# OpenServoCAN_Power_Board_V_1_0_1.net
KiCad netlist of a schematic drawn in EAGLE
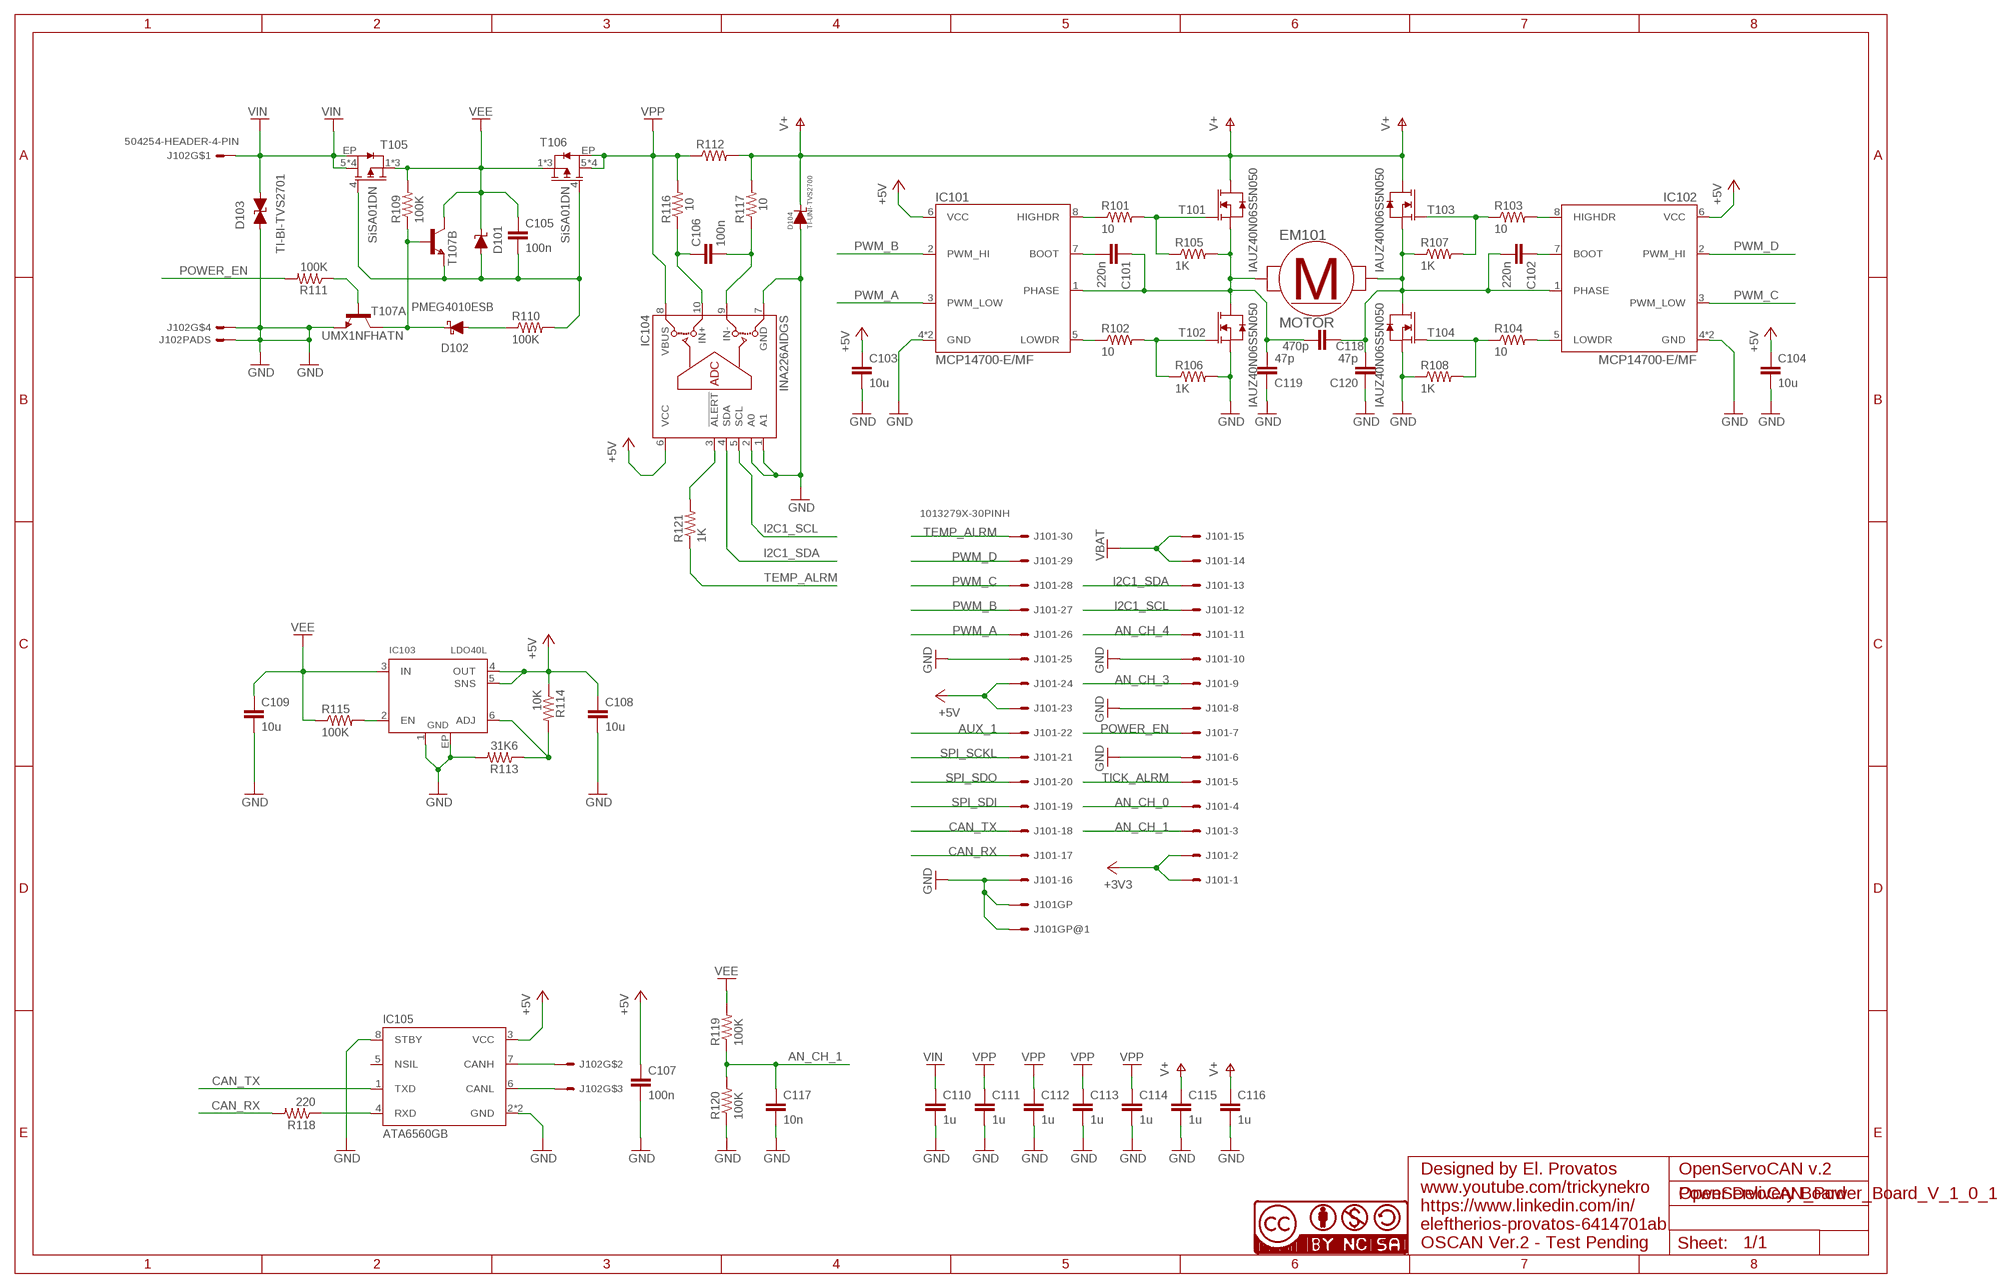
[diagram p0: schematic, sheet 1]

(export (version "E")
  (design (tool "Eeschema 10.0.6"))
  (components
    (comp (ref "C101")
      (value "220n")
      (footprint "eagle-import:0603_C")
      (libsource (lib "eagle-import") (part "C-EUC0603"))
    )
    (comp (ref "C102")
      (value "220n")
      (footprint "eagle-import:0603_C")
      (libsource (lib "eagle-import") (part "C-EUC0603"))
    )
    (comp (ref "C103")
      (value "10u")
      (footprint "eagle-import:0402_C")
      (libsource (lib "eagle-import") (part "C-EUC0402"))
    )
    (comp (ref "C104")
      (value "10u")
      (footprint "eagle-import:0402_C")
      (libsource (lib "eagle-import") (part "C-EUC0402"))
    )
    (comp (ref "C105")
      (value "100n")
      (footprint "eagle-import:0402_C")
      (libsource (lib "eagle-import") (part "C-EUC0402"))
    )
    (comp (ref "C106")
      (value "100n")
      (footprint "eagle-import:0402_C")
      (libsource (lib "eagle-import") (part "C-EUC0402"))
    )
    (comp (ref "C107")
      (value "100n")
      (footprint "eagle-import:0402_C")
      (libsource (lib "eagle-import") (part "C-EUC0402"))
    )
    (comp (ref "C108")
      (value "10u")
      (footprint "eagle-import:0402_C")
      (libsource (lib "eagle-import") (part "C-EUC0402"))
    )
    (comp (ref "C109")
      (value "10u")
      (footprint "eagle-import:0402_C")
      (libsource (lib "eagle-import") (part "C-EUC0402"))
    )
    (comp (ref "C110")
      (value "1u")
      (footprint "eagle-import:0603_C")
      (libsource (lib "eagle-import") (part "C-EUC0603"))
    )
    (comp (ref "C111")
      (value "1u")
      (footprint "eagle-import:0603_C")
      (libsource (lib "eagle-import") (part "C-EUC0603"))
    )
    (comp (ref "C112")
      (value "1u")
      (footprint "eagle-import:0603_C")
      (libsource (lib "eagle-import") (part "C-EUC0603"))
    )
    (comp (ref "C113")
      (value "1u")
      (footprint "eagle-import:0603_C")
      (libsource (lib "eagle-import") (part "C-EUC0603"))
    )
    (comp (ref "C114")
      (value "1u")
      (footprint "eagle-import:0603_C")
      (libsource (lib "eagle-import") (part "C-EUC0603"))
    )
    (comp (ref "C115")
      (value "1u")
      (footprint "eagle-import:0603_C")
      (libsource (lib "eagle-import") (part "C-EUC0603"))
    )
    (comp (ref "C116")
      (value "1u")
      (footprint "eagle-import:0603_C")
      (libsource (lib "eagle-import") (part "C-EUC0603"))
    )
    (comp (ref "C117")
      (value "10n")
      (footprint "eagle-import:0402_C")
      (libsource (lib "eagle-import") (part "C-EUC0402"))
    )
    (comp (ref "C118")
      (value "470p")
      (footprint "eagle-import:1206_C")
      (libsource (lib "eagle-import") (part "C-EUC1206"))
    )
    (comp (ref "C119")
      (value "47p")
      (footprint "eagle-import:1206_C")
      (libsource (lib "eagle-import") (part "C-EUC1206"))
    )
    (comp (ref "C120")
      (value "47p")
      (footprint "eagle-import:1206_C")
      (libsource (lib "eagle-import") (part "C-EUC1206"))
    )
    (comp (ref "D101")
      (value "DDZ12CSF")
      (footprint "eagle-import:SOD-323")
      (libsource (lib "eagle-import") (part "DDZ12CSF"))
    )
    (comp (ref "D102")
      (value "PMEG4010ESB")
      (footprint "eagle-import:DSN1006-2")
      (libsource (lib "eagle-import") (part "PMEG4010ESB"))
    )
    (comp (ref "D103")
      (value "TI-BI-TVS2701")
      (footprint "eagle-import:VSON-8-DRB0008A")
      (libsource (lib "eagle-import") (part "TI-BI-TVS2701"))
    )
    (comp (ref "D104")
      (value "TI-UNI-TVS2700")
      (footprint "eagle-import:WSON-6")
      (libsource (lib "eagle-import") (part "TI-UNI-TVS2700"))
    )
    (comp (ref "EM101")
      (value "MOTOR")
      (footprint "eagle-import:RF-020TH-10210")
      (libsource (lib "eagle-import") (part "MOTOR"))
    )
    (comp (ref "IC101")
      (value "MCP14700-E/MF")
      (footprint "eagle-import:DFN_8_3X3X09_MF_MICROCHIP")
      (libsource (lib "eagle-import") (part "MCP14700-E/MF"))
    )
    (comp (ref "IC102")
      (value "MCP14700-E/MF")
      (footprint "eagle-import:DFN_8_3X3X09_MF_MICROCHIP")
      (libsource (lib "eagle-import") (part "MCP14700-E/MF"))
    )
    (comp (ref "IC103")
      (value "LDO40L")
      (footprint "eagle-import:DFN6-3X3")
      (libsource (lib "eagle-import") (part "LDO40L-ADJ"))
    )
    (comp (ref "IC104")
      (value "INA226AIDGS")
      (footprint "eagle-import:VSSOP-10")
      (libsource (lib "eagle-import") (part "INA226AIDGS"))
    )
    (comp (ref "IC105")
      (value "ATA6560GB")
      (footprint "eagle-import:VDFN-8-EP")
      (libsource (lib "eagle-import") (part "ATA6560GB"))
    )
    (comp (ref "J101")
      (value "1013279X-30PINH")
      (footprint "eagle-import:10132797-30")
      (libsource (lib "eagle-import") (part "1013279X-30PINH"))
    )
    (comp (ref "J102")
      (value "504254-HEADER-4-PIN")
      (footprint "eagle-import:504254")
      (libsource (lib "eagle-import") (part "504254-HEADER-4-PIN"))
    )
    (comp (ref "R101")
      (value "10")
      (footprint "eagle-import:0402_R")
      (libsource (lib "eagle-import") (part "R-USR0402"))
    )
    (comp (ref "R102")
      (value "10")
      (footprint "eagle-import:0402_R")
      (libsource (lib "eagle-import") (part "R-USR0402"))
    )
    (comp (ref "R103")
      (value "10")
      (footprint "eagle-import:0402_R")
      (libsource (lib "eagle-import") (part "R-USR0402"))
    )
    (comp (ref "R104")
      (value "10")
      (footprint "eagle-import:0402_R")
      (libsource (lib "eagle-import") (part "R-USR0402"))
    )
    (comp (ref "R105")
      (value "1K")
      (footprint "eagle-import:0402_R")
      (libsource (lib "eagle-import") (part "R-USR0402"))
    )
    (comp (ref "R106")
      (value "1K")
      (footprint "eagle-import:0402_R")
      (libsource (lib "eagle-import") (part "R-USR0402"))
    )
    (comp (ref "R107")
      (value "1K")
      (footprint "eagle-import:0402_R")
      (libsource (lib "eagle-import") (part "R-USR0402"))
    )
    (comp (ref "R108")
      (value "1K")
      (footprint "eagle-import:0402_R")
      (libsource (lib "eagle-import") (part "R-USR0402"))
    )
    (comp (ref "R109")
      (value "100K")
      (footprint "eagle-import:0402_R")
      (libsource (lib "eagle-import") (part "R-USR0402"))
    )
    (comp (ref "R110")
      (value "100K")
      (footprint "eagle-import:0402_R")
      (libsource (lib "eagle-import") (part "R-USR0402"))
    )
    (comp (ref "R111")
      (value "100K")
      (footprint "eagle-import:0402_R")
      (libsource (lib "eagle-import") (part "R-USR0402"))
    )
    (comp (ref "R112")
      (value "TLR2HW-R-US-SENSE")
      (footprint "eagle-import:TLR2HW")
      (libsource (lib "eagle-import") (part "TLR2HW-R-US-SENSE"))
    )
    (comp (ref "R113")
      (value "31K6")
      (footprint "eagle-import:0402_R")
      (libsource (lib "eagle-import") (part "R-USR0402"))
    )
    (comp (ref "R114")
      (value "10K")
      (footprint "eagle-import:0402_R")
      (libsource (lib "eagle-import") (part "R-USR0402"))
    )
    (comp (ref "R115")
      (value "100K")
      (footprint "eagle-import:0402_R")
      (libsource (lib "eagle-import") (part "R-USR0402"))
    )
    (comp (ref "R116")
      (value "10")
      (footprint "eagle-import:0402_R")
      (libsource (lib "eagle-import") (part "R-USR0402"))
    )
    (comp (ref "R117")
      (value "10")
      (footprint "eagle-import:0402_R")
      (libsource (lib "eagle-import") (part "R-USR0402"))
    )
    (comp (ref "R118")
      (value "220")
      (footprint "eagle-import:0402_R")
      (libsource (lib "eagle-import") (part "R-USR0402"))
    )
    (comp (ref "R119")
      (value "100K")
      (footprint "eagle-import:0402_R")
      (libsource (lib "eagle-import") (part "R-USR0402"))
    )
    (comp (ref "R120")
      (value "100K")
      (footprint "eagle-import:0402_R")
      (libsource (lib "eagle-import") (part "R-USR0402"))
    )
    (comp (ref "R121")
      (value "1K")
      (footprint "eagle-import:0402_R")
      (libsource (lib "eagle-import") (part "R-USR0402"))
    )
    (comp (ref "T101")
      (value "IAUZ40N06S5N050")
      (footprint "eagle-import:PG-TSDSON-8-33-INF")
      (libsource (lib "eagle-import") (part "IAUZ40N06S5N050"))
    )
    (comp (ref "T102")
      (value "IAUZ40N06S5N050")
      (footprint "eagle-import:PG-TSDSON-8-33-INF")
      (libsource (lib "eagle-import") (part "IAUZ40N06S5N050"))
    )
    (comp (ref "T103")
      (value "IAUZ40N06S5N050")
      (footprint "eagle-import:PG-TSDSON-8-33-INF")
      (libsource (lib "eagle-import") (part "IAUZ40N06S5N050"))
    )
    (comp (ref "T104")
      (value "IAUZ40N06S5N050")
      (footprint "eagle-import:PG-TSDSON-8-33-INF")
      (libsource (lib "eagle-import") (part "IAUZ40N06S5N050"))
    )
    (comp (ref "T105")
      (value "SiSA01DN")
      (footprint "eagle-import:POWERPAK-1212-8-SINGLE")
      (libsource (lib "eagle-import") (part "SISA01DN"))
    )
    (comp (ref "T106")
      (value "SiSA01DN")
      (footprint "eagle-import:POWERPAK-1212-8-SINGLE")
      (libsource (lib "eagle-import") (part "SISA01DN"))
    )
    (comp (ref "T107")
      (value "UMX1NFHATN")
      (footprint "eagle-import:SC-70-6")
      (libsource (lib "eagle-import") (part "UMX1NFHATN"))
    )
    (comp (ref "U$1")
      (value "CC-NC-BCNIX")
      (footprint "eagle-import:CC-NC-B_NIX")
      (libsource (lib "eagle-import") (part "CC-NC-BCNIX"))
    )
  )
  (nets
    (net (code "1") (name "+3V3") (class "Default")
      (node (ref "J101") (pin "1") (pinfunction "S_1") (pintype "passive"))
      (node (ref "J101") (pin "2") (pinfunction "S_2") (pintype "passive"))
    )
    (net (code "2") (name "+5V") (class "Default")
      (node (ref "C103") (pin "1") (pinfunction "1_1") (pintype "passive"))
      (node (ref "C104") (pin "1") (pinfunction "1_1") (pintype "passive"))
      (node (ref "C107") (pin "1") (pinfunction "1_1") (pintype "passive"))
      (node (ref "C108") (pin "1") (pinfunction "1_1") (pintype "passive"))
      (node (ref "IC101") (pin "6") (pinfunction "VCC_6") (pintype "bidirectional"))
      (node (ref "IC102") (pin "6") (pinfunction "VCC_6") (pintype "bidirectional"))
      (node (ref "IC103") (pin "4") (pinfunction "OUT_4") (pintype "bidirectional"))
      (node (ref "IC103") (pin "5") (pinfunction "SNS_5") (pintype "bidirectional"))
      (node (ref "IC104") (pin "6") (pinfunction "VCC_6") (pintype "bidirectional"))
      (node (ref "IC105") (pin "3") (pinfunction "VCC_3") (pintype "power_in"))
      (node (ref "J101") (pin "23") (pinfunction "S_23") (pintype "passive"))
      (node (ref "J101") (pin "24") (pinfunction "S_24") (pintype "passive"))
      (node (ref "R114") (pin "1") (pinfunction "1_1") (pintype "passive"))
    )
    (net (code "3") (name "/AN_CH_0") (class "Default")
      (node (ref "J101") (pin "4") (pinfunction "S_4") (pintype "passive"))
    )
    (net (code "4") (name "/AN_CH_1") (class "Default")
      (node (ref "C117") (pin "1") (pinfunction "1_1") (pintype "passive"))
      (node (ref "J101") (pin "3") (pinfunction "S_3") (pintype "passive"))
      (node (ref "R119") (pin "1") (pinfunction "1_1") (pintype "passive"))
      (node (ref "R120") (pin "2") (pinfunction "2_2") (pintype "passive"))
    )
    (net (code "5") (name "/AN_CH_3") (class "Default")
      (node (ref "J101") (pin "9") (pinfunction "S_9") (pintype "passive"))
    )
    (net (code "6") (name "/AN_CH_4") (class "Default")
      (node (ref "J101") (pin "11") (pinfunction "S_11") (pintype "passive"))
    )
    (net (code "7") (name "/AUX_1") (class "Default")
      (node (ref "J101") (pin "22") (pinfunction "S_22") (pintype "passive"))
    )
    (net (code "8") (name "/CAN_RX") (class "Default")
      (node (ref "J101") (pin "17") (pinfunction "S_17") (pintype "passive"))
      (node (ref "R118") (pin "2") (pinfunction "2_2") (pintype "passive"))
    )
    (net (code "9") (name "/CAN_TX") (class "Default")
      (node (ref "IC105") (pin "1") (pinfunction "TXD_1") (pintype "input"))
      (node (ref "J101") (pin "18") (pinfunction "S_18") (pintype "passive"))
    )
    (net (code "10") (name "/I2C1_SCL") (class "Default")
      (node (ref "IC104") (pin "5") (pinfunction "SCL_5") (pintype "bidirectional"))
      (node (ref "J101") (pin "12") (pinfunction "S_12") (pintype "passive"))
    )
    (net (code "11") (name "/I2C1_SDA") (class "Default")
      (node (ref "IC104") (pin "4") (pinfunction "SDA_4") (pintype "bidirectional"))
      (node (ref "J101") (pin "13") (pinfunction "S_13") (pintype "passive"))
    )
    (net (code "12") (name "/POWER_EN") (class "Default")
      (node (ref "J101") (pin "7") (pinfunction "S_7") (pintype "passive"))
      (node (ref "R111") (pin "2") (pinfunction "2_2") (pintype "passive"))
    )
    (net (code "13") (name "/PWM_A") (class "Default")
      (node (ref "IC101") (pin "3") (pinfunction "PWM_LOW_3") (pintype "bidirectional"))
      (node (ref "J101") (pin "26") (pinfunction "S_26") (pintype "passive"))
    )
    (net (code "14") (name "/PWM_B") (class "Default")
      (node (ref "IC101") (pin "2") (pinfunction "PWM_HI_2") (pintype "bidirectional"))
      (node (ref "J101") (pin "27") (pinfunction "S_27") (pintype "passive"))
    )
    (net (code "15") (name "/PWM_C") (class "Default")
      (node (ref "IC102") (pin "3") (pinfunction "PWM_LOW_3") (pintype "bidirectional"))
      (node (ref "J101") (pin "28") (pinfunction "S_28") (pintype "passive"))
    )
    (net (code "16") (name "/PWM_D") (class "Default")
      (node (ref "IC102") (pin "2") (pinfunction "PWM_HI_2") (pintype "bidirectional"))
      (node (ref "J101") (pin "29") (pinfunction "S_29") (pintype "passive"))
    )
    (net (code "17") (name "/SPI_SCKL") (class "Default")
      (node (ref "J101") (pin "21") (pinfunction "S_21") (pintype "passive"))
    )
    (net (code "18") (name "/SPI_SDI") (class "Default")
      (node (ref "J101") (pin "19") (pinfunction "S_19") (pintype "passive"))
    )
    (net (code "19") (name "/SPI_SDO") (class "Default")
      (node (ref "J101") (pin "20") (pinfunction "S_20") (pintype "passive"))
    )
    (net (code "20") (name "/TEMP_ALRM") (class "Default")
      (node (ref "J101") (pin "30") (pinfunction "S_30") (pintype "passive"))
      (node (ref "R121") (pin "1") (pinfunction "1_1") (pintype "passive"))
    )
    (net (code "21") (name "/TICK_ALRM") (class "Default")
      (node (ref "J101") (pin "5") (pinfunction "S_5") (pintype "passive"))
    )
    (net (code "22") (name "GND") (class "Default")
      (node (ref "C103") (pin "2") (pinfunction "2_2") (pintype "passive"))
      (node (ref "C104") (pin "2") (pinfunction "2_2") (pintype "passive"))
      (node (ref "C107") (pin "2") (pinfunction "2_2") (pintype "passive"))
      (node (ref "C108") (pin "2") (pinfunction "2_2") (pintype "passive"))
      (node (ref "C109") (pin "2") (pinfunction "2_2") (pintype "passive"))
      (node (ref "C110") (pin "2") (pinfunction "2_2") (pintype "passive"))
      (node (ref "C111") (pin "2") (pinfunction "2_2") (pintype "passive"))
      (node (ref "C112") (pin "2") (pinfunction "2_2") (pintype "passive"))
      (node (ref "C113") (pin "2") (pinfunction "2_2") (pintype "passive"))
      (node (ref "C114") (pin "2") (pinfunction "2_2") (pintype "passive"))
      (node (ref "C115") (pin "2") (pinfunction "2_2") (pintype "passive"))
      (node (ref "C116") (pin "2") (pinfunction "2_2") (pintype "passive"))
      (node (ref "C117") (pin "2") (pinfunction "2_2") (pintype "passive"))
      (node (ref "C119") (pin "1") (pinfunction "1_1") (pintype "passive"))
      (node (ref "C120") (pin "1") (pinfunction "1_1") (pintype "passive"))
      (node (ref "D103") (pin "5") (pinfunction "A_5") (pintype "bidirectional"))
      (node (ref "D103") (pin "6") (pinfunction "A_6") (pintype "bidirectional"))
      (node (ref "D103") (pin "7") (pinfunction "A_7") (pintype "bidirectional"))
      (node (ref "D103") (pin "8") (pinfunction "A_8") (pintype "bidirectional"))
      (node (ref "D104") (pin "1") (pinfunction "A_1") (pintype "bidirectional"))
      (node (ref "D104") (pin "2") (pinfunction "A_2") (pintype "bidirectional"))
      (node (ref "D104") (pin "3") (pinfunction "A_3") (pintype "bidirectional"))
      (node (ref "D104") (pin "EP") (pinfunction "A_EP") (pintype "bidirectional"))
      (node (ref "IC101") (pin "4") (pinfunction "GND_4") (pintype "bidirectional"))
      (node (ref "IC101") (pin "EP") (pinfunction "GND_EP") (pintype "bidirectional"))
      (node (ref "IC102") (pin "4") (pinfunction "GND_4") (pintype "bidirectional"))
      (node (ref "IC102") (pin "EP") (pinfunction "GND_EP") (pintype "bidirectional"))
      (node (ref "IC103") (pin "1") (pinfunction "GND_1") (pintype "bidirectional"))
      (node (ref "IC103") (pin "EP") (pinfunction "GND_EP") (pintype "bidirectional"))
      (node (ref "IC104") (pin "1") (pinfunction "A1_1") (pintype "bidirectional"))
      (node (ref "IC104") (pin "2") (pinfunction "A0_2") (pintype "bidirectional"))
      (node (ref "IC104") (pin "7") (pinfunction "GND_7") (pintype "bidirectional"))
      (node (ref "IC105") (pin "2") (pinfunction "GND_2") (pintype "power_in"))
      (node (ref "IC105") (pin "8") (pinfunction "STBY_8") (pintype "input"))
      (node (ref "IC105") (pin "EP") (pinfunction "GND_EP") (pintype "power_in"))
      (node (ref "J101") (pin "10") (pinfunction "S_10") (pintype "passive"))
      (node (ref "J101") (pin "16") (pinfunction "S_16") (pintype "passive"))
      (node (ref "J101") (pin "25") (pinfunction "S_25") (pintype "passive"))
      (node (ref "J101") (pin "6") (pinfunction "S_6") (pintype "passive"))
      (node (ref "J101") (pin "8") (pinfunction "S_8") (pintype "passive"))
      (node (ref "J101") (pin "EP@2") (pinfunction "S_EP@2") (pintype "passive"))
      (node (ref "J101") (pin "EP@↑1") (pinfunction "S_EP@↑1") (pintype "passive"))
      (node (ref "J102") (pin "4") (pinfunction "S_4") (pintype "passive"))
      (node (ref "J102") (pin "EP@1") (pinfunction "S_EP@1") (pintype "passive"))
      (node (ref "J102") (pin "EP@2") (pinfunction "S_EP@2") (pintype "passive"))
      (node (ref "J102") (pin "EP@3") (pinfunction "S_EP@3") (pintype "passive"))
      (node (ref "J102") (pin "EP@4") (pinfunction "S_EP@4") (pintype "passive"))
      (node (ref "R106") (pin "2") (pinfunction "2_2") (pintype "passive"))
      (node (ref "R108") (pin "1") (pinfunction "1_1") (pintype "passive"))
      (node (ref "R113") (pin "2") (pinfunction "2_2") (pintype "passive"))
      (node (ref "R120") (pin "1") (pinfunction "1_1") (pintype "passive"))
      (node (ref "T102") (pin "S") (pinfunction "S_S") (pintype "bidirectional"))
      (node (ref "T104") (pin "S") (pinfunction "S_S") (pintype "bidirectional"))
      (node (ref "T107") (pin "1") (pinfunction "E_1") (pintype "passive"))
    )
    (net (code "23") (name "Net-(D102-PadA)") (class "Default")
      (node (ref "D102") (pin "A") (pinfunction "A_A") (pintype "bidirectional"))
      (node (ref "R110") (pin "1") (pinfunction "1_1") (pintype "passive"))
    )
    (net (code "24") (name "Net-(IC101-BOOT)") (class "Default")
      (node (ref "C101") (pin "2") (pinfunction "2_2") (pintype "passive"))
      (node (ref "IC101") (pin "7") (pinfunction "BOOT_7") (pintype "bidirectional"))
    )
    (net (code "25") (name "Net-(IC101-HIGHDR)") (class "Default")
      (node (ref "IC101") (pin "8") (pinfunction "HIGHDR_8") (pintype "bidirectional"))
      (node (ref "R101") (pin "1") (pinfunction "1_1") (pintype "passive"))
    )
    (net (code "26") (name "Net-(IC101-LOWDR)") (class "Default")
      (node (ref "IC101") (pin "5") (pinfunction "LOWDR_5") (pintype "bidirectional"))
      (node (ref "R102") (pin "1") (pinfunction "1_1") (pintype "passive"))
    )
    (net (code "27") (name "Net-(IC101-PHASE)") (class "Default")
      (node (ref "C101") (pin "1") (pinfunction "1_1") (pintype "passive"))
      (node (ref "C118") (pin "2") (pinfunction "2_2") (pintype "passive"))
      (node (ref "C119") (pin "2") (pinfunction "2_2") (pintype "passive"))
      (node (ref "EM101") (pin "1B") (pinfunction "1_1B") (pintype "bidirectional"))
      (node (ref "EM101") (pin "1T") (pinfunction "1_1T") (pintype "bidirectional"))
      (node (ref "IC101") (pin "1") (pinfunction "PHASE_1") (pintype "bidirectional"))
      (node (ref "R105") (pin "2") (pinfunction "2_2") (pintype "passive"))
      (node (ref "T101") (pin "S") (pinfunction "S_S") (pintype "bidirectional"))
      (node (ref "T102") (pin "D") (pinfunction "D_D") (pintype "bidirectional"))
    )
    (net (code "28") (name "Net-(IC102-BOOT)") (class "Default")
      (node (ref "C102") (pin "1") (pinfunction "1_1") (pintype "passive"))
      (node (ref "IC102") (pin "7") (pinfunction "BOOT_7") (pintype "bidirectional"))
    )
    (net (code "29") (name "Net-(IC102-HIGHDR)") (class "Default")
      (node (ref "IC102") (pin "8") (pinfunction "HIGHDR_8") (pintype "bidirectional"))
      (node (ref "R103") (pin "2") (pinfunction "2_2") (pintype "passive"))
    )
    (net (code "30") (name "Net-(IC102-LOWDR)") (class "Default")
      (node (ref "IC102") (pin "5") (pinfunction "LOWDR_5") (pintype "bidirectional"))
      (node (ref "R104") (pin "2") (pinfunction "2_2") (pintype "passive"))
    )
    (net (code "31") (name "Net-(IC102-PHASE)") (class "Default")
      (node (ref "C102") (pin "2") (pinfunction "2_2") (pintype "passive"))
      (node (ref "C118") (pin "1") (pinfunction "1_1") (pintype "passive"))
      (node (ref "C120") (pin "2") (pinfunction "2_2") (pintype "passive"))
      (node (ref "EM101") (pin "2B") (pinfunction "2_2B") (pintype "bidirectional"))
      (node (ref "EM101") (pin "2T") (pinfunction "2_2T") (pintype "bidirectional"))
      (node (ref "IC102") (pin "1") (pinfunction "PHASE_1") (pintype "bidirectional"))
      (node (ref "R107") (pin "1") (pinfunction "1_1") (pintype "passive"))
      (node (ref "T103") (pin "S") (pinfunction "S_S") (pintype "bidirectional"))
      (node (ref "T104") (pin "D") (pinfunction "D_D") (pintype "bidirectional"))
    )
    (net (code "32") (name "Net-(IC103-ADJ)") (class "Default")
      (node (ref "IC103") (pin "6") (pinfunction "ADJ_6") (pintype "bidirectional"))
      (node (ref "R113") (pin "1") (pinfunction "1_1") (pintype "passive"))
      (node (ref "R114") (pin "2") (pinfunction "2_2") (pintype "passive"))
    )
    (net (code "33") (name "Net-(IC103-EN)") (class "Default")
      (node (ref "IC103") (pin "2") (pinfunction "EN_2") (pintype "bidirectional"))
      (node (ref "R115") (pin "2") (pinfunction "2_2") (pintype "passive"))
    )
    (net (code "34") (name "Net-(IC104-IN+)") (class "Default")
      (node (ref "C106") (pin "1") (pinfunction "1_1") (pintype "passive"))
      (node (ref "IC104") (pin "10") (pinfunction "IN+_10") (pintype "bidirectional"))
      (node (ref "R116") (pin "1") (pinfunction "1_1") (pintype "passive"))
    )
    (net (code "35") (name "Net-(IC104-IN-)") (class "Default")
      (node (ref "C106") (pin "2") (pinfunction "2_2") (pintype "passive"))
      (node (ref "IC104") (pin "9") (pinfunction "IN-_9") (pintype "bidirectional"))
      (node (ref "R117") (pin "1") (pinfunction "1_1") (pintype "passive"))
    )
    (net (code "36") (name "Net-(IC104-~{ALERT})") (class "Default")
      (node (ref "IC104") (pin "3") (pinfunction "~{ALERT}_3") (pintype "bidirectional"))
      (node (ref "R121") (pin "2") (pinfunction "2_2") (pintype "passive"))
    )
    (net (code "37") (name "Net-(IC105-CANH)") (class "Default")
      (node (ref "IC105") (pin "7") (pinfunction "CANH_7") (pintype "bidirectional"))
      (node (ref "J102") (pin "2") (pinfunction "S_2") (pintype "passive"))
    )
    (net (code "38") (name "Net-(IC105-CANL)") (class "Default")
      (node (ref "IC105") (pin "6") (pinfunction "CANL_6") (pintype "bidirectional"))
      (node (ref "J102") (pin "3") (pinfunction "S_3") (pintype "passive"))
    )
    (net (code "39") (name "Net-(IC105-RXD)") (class "Default")
      (node (ref "IC105") (pin "4") (pinfunction "RXD_4") (pintype "output"))
      (node (ref "R118") (pin "1") (pinfunction "1_1") (pintype "passive"))
    )
    (net (code "40") (name "Net-(R101-Pad2)") (class "Default")
      (node (ref "R101") (pin "2") (pinfunction "2_2") (pintype "passive"))
      (node (ref "R105") (pin "1") (pinfunction "1_1") (pintype "passive"))
      (node (ref "T101") (pin "G") (pinfunction "G_G") (pintype "bidirectional"))
    )
    (net (code "41") (name "Net-(R102-Pad2)") (class "Default")
      (node (ref "R102") (pin "2") (pinfunction "2_2") (pintype "passive"))
      (node (ref "R106") (pin "1") (pinfunction "1_1") (pintype "passive"))
      (node (ref "T102") (pin "G") (pinfunction "G_G") (pintype "bidirectional"))
    )
    (net (code "42") (name "Net-(R103-Pad1)") (class "Default")
      (node (ref "R103") (pin "1") (pinfunction "1_1") (pintype "passive"))
      (node (ref "R107") (pin "2") (pinfunction "2_2") (pintype "passive"))
      (node (ref "T103") (pin "G") (pinfunction "G_G") (pintype "bidirectional"))
    )
    (net (code "43") (name "Net-(R104-Pad1)") (class "Default")
      (node (ref "R104") (pin "1") (pinfunction "1_1") (pintype "passive"))
      (node (ref "R108") (pin "2") (pinfunction "2_2") (pintype "passive"))
      (node (ref "T104") (pin "G") (pinfunction "G_G") (pintype "bidirectional"))
    )
    (net (code "44") (name "Net-(T105-G)") (class "Default")
      (node (ref "C105") (pin "2") (pinfunction "2_2") (pintype "passive"))
      (node (ref "D101") (pin "A") (pinfunction "A_A") (pintype "bidirectional"))
      (node (ref "R110") (pin "2") (pinfunction "2_2") (pintype "passive"))
      (node (ref "T105") (pin "4") (pinfunction "G_4") (pintype "bidirectional"))
      (node (ref "T106") (pin "4") (pinfunction "G_4") (pintype "bidirectional"))
      (node (ref "T107") (pin "4") (pinfunction "E_4") (pintype "passive"))
    )
    (net (code "45") (name "Net-(T107A-B)") (class "Default")
      (node (ref "R111") (pin "1") (pinfunction "1_1") (pintype "passive"))
      (node (ref "T107") (pin "2") (pinfunction "B_2") (pintype "passive"))
    )
    (net (code "46") (name "Net-(T107A-C)") (class "Default")
      (node (ref "D102") (pin "K") (pinfunction "K_K") (pintype "bidirectional"))
      (node (ref "R109") (pin "1") (pinfunction "1_1") (pintype "passive"))
      (node (ref "T107") (pin "5") (pinfunction "B_5") (pintype "passive"))
      (node (ref "T107") (pin "6") (pinfunction "C_6") (pintype "passive"))
    )
    (net (code "47") (name "V+") (class "Default")
      (node (ref "C115") (pin "1") (pinfunction "1_1") (pintype "passive"))
      (node (ref "C116") (pin "1") (pinfunction "1_1") (pintype "passive"))
      (node (ref "D104") (pin "4") (pinfunction "K_4") (pintype "bidirectional"))
      (node (ref "D104") (pin "5") (pinfunction "K_5") (pintype "bidirectional"))
      (node (ref "D104") (pin "6") (pinfunction "K_6") (pintype "bidirectional"))
      (node (ref "R112") (pin "2") (pinfunction "2_2") (pintype "passive"))
      (node (ref "R117") (pin "2") (pinfunction "2_2") (pintype "passive"))
      (node (ref "T101") (pin "D") (pinfunction "D_D") (pintype "bidirectional"))
      (node (ref "T103") (pin "D") (pinfunction "D_D") (pintype "bidirectional"))
    )
    (net (code "48") (name "VBAT") (class "Default")
      (node (ref "J101") (pin "14") (pinfunction "S_14") (pintype "passive"))
      (node (ref "J101") (pin "15") (pinfunction "S_15") (pintype "passive"))
    )
    (net (code "49") (name "VEE") (class "Default")
      (node (ref "C105") (pin "1") (pinfunction "1_1") (pintype "passive"))
      (node (ref "C109") (pin "1") (pinfunction "1_1") (pintype "passive"))
      (node (ref "D101") (pin "K") (pinfunction "K_K") (pintype "bidirectional"))
      (node (ref "IC103") (pin "3") (pinfunction "IN_3") (pintype "bidirectional"))
      (node (ref "R109") (pin "2") (pinfunction "2_2") (pintype "passive"))
      (node (ref "R115") (pin "1") (pinfunction "1_1") (pintype "passive"))
      (node (ref "R119") (pin "2") (pinfunction "2_2") (pintype "passive"))
      (node (ref "T105") (pin "1") (pinfunction "S_1") (pintype "bidirectional"))
      (node (ref "T105") (pin "2") (pinfunction "S_2") (pintype "bidirectional"))
      (node (ref "T105") (pin "3") (pinfunction "S_3") (pintype "bidirectional"))
      (node (ref "T106") (pin "1") (pinfunction "S_1") (pintype "bidirectional"))
      (node (ref "T106") (pin "2") (pinfunction "S_2") (pintype "bidirectional"))
      (node (ref "T106") (pin "3") (pinfunction "S_3") (pintype "bidirectional"))
      (node (ref "T107") (pin "3") (pinfunction "C_3") (pintype "passive"))
    )
    (net (code "50") (name "VIN") (class "Default")
      (node (ref "C110") (pin "1") (pinfunction "1_1") (pintype "passive"))
      (node (ref "D103") (pin "1") (pinfunction "K_1") (pintype "bidirectional"))
      (node (ref "D103") (pin "2") (pinfunction "K_2") (pintype "bidirectional"))
      (node (ref "D103") (pin "3") (pinfunction "K_3") (pintype "bidirectional"))
      (node (ref "D103") (pin "4") (pinfunction "K_4") (pintype "bidirectional"))
      (node (ref "J102") (pin "1") (pinfunction "S_1") (pintype "passive"))
      (node (ref "T105") (pin "5") (pinfunction "D_5") (pintype "bidirectional"))
      (node (ref "T105") (pin "6") (pinfunction "D_6") (pintype "bidirectional"))
      (node (ref "T105") (pin "7") (pinfunction "D_7") (pintype "bidirectional"))
      (node (ref "T105") (pin "8") (pinfunction "D_8") (pintype "bidirectional"))
      (node (ref "T105") (pin "EP") (pinfunction "D_EP") (pintype "bidirectional"))
    )
    (net (code "51") (name "VPP") (class "Default")
      (node (ref "C111") (pin "1") (pinfunction "1_1") (pintype "passive"))
      (node (ref "C112") (pin "1") (pinfunction "1_1") (pintype "passive"))
      (node (ref "C113") (pin "1") (pinfunction "1_1") (pintype "passive"))
      (node (ref "C114") (pin "1") (pinfunction "1_1") (pintype "passive"))
      (node (ref "IC104") (pin "8") (pinfunction "VBUS_8") (pintype "bidirectional"))
      (node (ref "R112") (pin "1") (pinfunction "1_1") (pintype "passive"))
      (node (ref "R116") (pin "2") (pinfunction "2_2") (pintype "passive"))
      (node (ref "T106") (pin "5") (pinfunction "D_5") (pintype "bidirectional"))
      (node (ref "T106") (pin "6") (pinfunction "D_6") (pintype "bidirectional"))
      (node (ref "T106") (pin "7") (pinfunction "D_7") (pintype "bidirectional"))
      (node (ref "T106") (pin "8") (pinfunction "D_8") (pintype "bidirectional"))
      (node (ref "T106") (pin "EP") (pinfunction "D_EP") (pintype "bidirectional"))
    )
    (net (code "52") (name "unconnected-(IC105-NSIL-Pad5)") (class "Default")
      (node (ref "IC105") (pin "5") (pinfunction "NSIL_5") (pintype "input"))
    )
  )
)
